# Audio-2.net
KiCad netlist of a schematic drawn in EAGLE
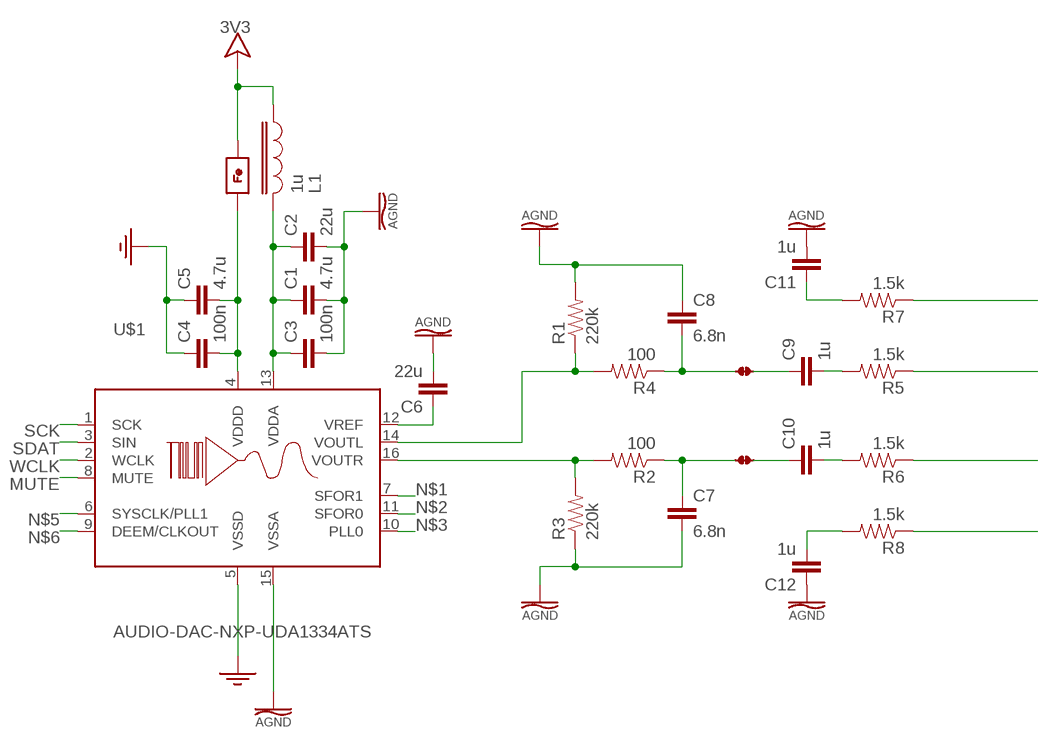
[diagram p0: schematic, sheet 1]

(export (version "E")
  (design (tool "Eeschema 10.0.6"))
  (components
    (comp (ref "C1")
      (value "4.7u")
      (footprint "eagle-import:0805-WIDE")
      (libsource (lib "eagle-import") (part "CAP-0805-WIDE"))
    )
    (comp (ref "C2")
      (value "22u")
      (footprint "eagle-import:1206-MIN")
      (libsource (lib "eagle-import") (part "CAP-1206-MIN"))
    )
    (comp (ref "C3")
      (value "100n")
      (footprint "eagle-import:0402")
      (libsource (lib "eagle-import") (part "CAP-0402"))
    )
    (comp (ref "C4")
      (value "100n")
      (footprint "eagle-import:0402")
      (libsource (lib "eagle-import") (part "CAP-0402"))
    )
    (comp (ref "C5")
      (value "4.7u")
      (footprint "eagle-import:0805-WIDE")
      (libsource (lib "eagle-import") (part "CAP-0805-WIDE"))
    )
    (comp (ref "C6")
      (value "22u")
      (footprint "eagle-import:1206-MIN")
      (libsource (lib "eagle-import") (part "CAP-1206-MIN"))
    )
    (comp (ref "C7")
      (value "6.8n")
      (footprint "eagle-import:0603")
      (libsource (lib "eagle-import") (part "CAP-0603"))
    )
    (comp (ref "C8")
      (value "6.8n")
      (footprint "eagle-import:0603")
      (libsource (lib "eagle-import") (part "CAP-0603"))
    )
    (comp (ref "C9")
      (value "1u")
      (footprint "eagle-import:0603")
      (libsource (lib "eagle-import") (part "CAP-0603"))
    )
    (comp (ref "C10")
      (value "1u")
      (footprint "eagle-import:0603")
      (libsource (lib "eagle-import") (part "CAP-0603"))
    )
    (comp (ref "C11")
      (value "1u")
      (footprint "eagle-import:0603")
      (libsource (lib "eagle-import") (part "CAP-0603"))
    )
    (comp (ref "C12")
      (value "1u")
      (footprint "eagle-import:0603")
      (libsource (lib "eagle-import") (part "CAP-0603"))
    )
    (comp (ref "FB1")
      (value "FERRITE-BEAD-0603-MIN")
      (footprint "eagle-import:0603-MIN")
      (libsource (lib "eagle-import") (part "FERRITE-BEAD-0603-MIN"))
    )
    (comp (ref "J1")
      (value "JUMPER-0805")
      (footprint "eagle-import:0805-JUMPER")
      (libsource (lib "eagle-import") (part "JUMPER-0805"))
    )
    (comp (ref "J2")
      (value "JUMPER-0805")
      (footprint "eagle-import:0805-JUMPER")
      (libsource (lib "eagle-import") (part "JUMPER-0805"))
    )
    (comp (ref "L1")
      (value "1u")
      (footprint "eagle-import:0805-MIN")
      (libsource (lib "eagle-import") (part "INDUCTOR-0805-MIN"))
    )
    (comp (ref "R1")
      (value "220k")
      (footprint "eagle-import:0603")
      (libsource (lib "eagle-import") (part "RESISTOR-0603"))
    )
    (comp (ref "R2")
      (value "100")
      (footprint "eagle-import:0603")
      (libsource (lib "eagle-import") (part "RESISTOR-0603"))
    )
    (comp (ref "R3")
      (value "220k")
      (footprint "eagle-import:0603")
      (libsource (lib "eagle-import") (part "RESISTOR-0603"))
    )
    (comp (ref "R4")
      (value "100")
      (footprint "eagle-import:0603")
      (libsource (lib "eagle-import") (part "RESISTOR-0603"))
    )
    (comp (ref "R5")
      (value "1.5k")
      (footprint "eagle-import:0603")
      (libsource (lib "eagle-import") (part "RESISTOR-0603"))
    )
    (comp (ref "R6")
      (value "1.5k")
      (footprint "eagle-import:0603")
      (libsource (lib "eagle-import") (part "RESISTOR-0603"))
    )
    (comp (ref "R7")
      (value "1.5k")
      (footprint "eagle-import:0603")
      (libsource (lib "eagle-import") (part "RESISTOR-0603"))
    )
    (comp (ref "R8")
      (value "1.5k")
      (footprint "eagle-import:0603")
      (libsource (lib "eagle-import") (part "RESISTOR-0603"))
    )
    (comp (ref "U$1")
      (value "AUDIO-DAC-NXP-UDA1334ATS")
      (footprint "eagle-import:TSSOP16")
      (libsource (lib "eagle-import") (part "AUDIO-DAC-NXP-UDA1334ATS"))
    )
  )
  (nets
    (net (code "1") (name "/MUTE") (class "Default")
      (node (ref "U$1") (pin "8") (pinfunction "MUTE_8") (pintype "bidirectional"))
    )
    (net (code "2") (name "/N$1") (class "Default")
      (node (ref "U$1") (pin "7") (pinfunction "SFOR1_7") (pintype "bidirectional"))
    )
    (net (code "3") (name "/N$2") (class "Default")
      (node (ref "U$1") (pin "11") (pinfunction "SFOR0_11") (pintype "bidirectional"))
    )
    (net (code "4") (name "/N$3") (class "Default")
      (node (ref "U$1") (pin "10") (pinfunction "PLL0_10") (pintype "bidirectional"))
    )
    (net (code "5") (name "/N$5") (class "Default")
      (node (ref "U$1") (pin "6") (pinfunction "SYSCLK/PLL1_6") (pintype "bidirectional"))
    )
    (net (code "6") (name "/N$6") (class "Default")
      (node (ref "U$1") (pin "9") (pinfunction "DEEM/CLKOUT_9") (pintype "bidirectional"))
    )
    (net (code "7") (name "/SCK") (class "Default")
      (node (ref "U$1") (pin "1") (pinfunction "SCK_1") (pintype "bidirectional"))
    )
    (net (code "8") (name "/SDAT") (class "Default")
      (node (ref "U$1") (pin "3") (pinfunction "SIN_3") (pintype "bidirectional"))
    )
    (net (code "9") (name "/WCLK") (class "Default")
      (node (ref "U$1") (pin "2") (pinfunction "WCLK_2") (pintype "bidirectional"))
    )
    (net (code "10") (name "AGND") (class "Default")
      (node (ref "C1") (pin "1") (pinfunction "1_1") (pintype "bidirectional"))
      (node (ref "C11") (pin "1") (pinfunction "1_1") (pintype "bidirectional"))
      (node (ref "C12") (pin "2") (pinfunction "2_2") (pintype "bidirectional"))
      (node (ref "C2") (pin "1") (pinfunction "1_1") (pintype "bidirectional"))
      (node (ref "C3") (pin "1") (pinfunction "1_1") (pintype "bidirectional"))
      (node (ref "C6") (pin "1") (pinfunction "1_1") (pintype "bidirectional"))
      (node (ref "C7") (pin "1") (pinfunction "1_1") (pintype "bidirectional"))
      (node (ref "C8") (pin "2") (pinfunction "2_2") (pintype "bidirectional"))
      (node (ref "R1") (pin "2") (pinfunction "2_2") (pintype "passive"))
      (node (ref "R3") (pin "1") (pinfunction "1_1") (pintype "passive"))
      (node (ref "U$1") (pin "15") (pinfunction "VSSA_15") (pintype "bidirectional"))
    )
    (net (code "11") (name "GND") (class "Default")
      (node (ref "C4") (pin "2") (pinfunction "2_2") (pintype "bidirectional"))
      (node (ref "C5") (pin "2") (pinfunction "2_2") (pintype "bidirectional"))
      (node (ref "U$1") (pin "5") (pinfunction "VSSD_5") (pintype "bidirectional"))
    )
    (net (code "12") (name "Net-(C7-Pad2)") (class "Default")
      (node (ref "C7") (pin "2") (pinfunction "2_2") (pintype "bidirectional"))
      (node (ref "J2") (pin "1") (pinfunction "1_1") (pintype "bidirectional"))
      (node (ref "R2") (pin "1") (pinfunction "1_1") (pintype "passive"))
    )
    (net (code "13") (name "Net-(C8-Pad1)") (class "Default")
      (node (ref "C8") (pin "1") (pinfunction "1_1") (pintype "bidirectional"))
      (node (ref "J1") (pin "1") (pinfunction "1_1") (pintype "bidirectional"))
      (node (ref "R4") (pin "1") (pinfunction "1_1") (pintype "passive"))
    )
    (net (code "14") (name "Net-(C9-Pad1)") (class "Default")
      (node (ref "C9") (pin "1") (pinfunction "1_1") (pintype "bidirectional"))
      (node (ref "R5") (pin "2") (pinfunction "2_2") (pintype "passive"))
    )
    (net (code "15") (name "Net-(C9-Pad2)") (class "Default")
      (node (ref "C9") (pin "2") (pinfunction "2_2") (pintype "bidirectional"))
      (node (ref "J1") (pin "2") (pinfunction "2_2") (pintype "bidirectional"))
    )
    (net (code "16") (name "Net-(C10-Pad1)") (class "Default")
      (node (ref "C10") (pin "1") (pinfunction "1_1") (pintype "bidirectional"))
      (node (ref "R6") (pin "2") (pinfunction "2_2") (pintype "passive"))
    )
    (net (code "17") (name "Net-(C10-Pad2)") (class "Default")
      (node (ref "C10") (pin "2") (pinfunction "2_2") (pintype "bidirectional"))
      (node (ref "J2") (pin "2") (pinfunction "2_2") (pintype "bidirectional"))
    )
    (net (code "18") (name "Net-(C11-Pad2)") (class "Default")
      (node (ref "C11") (pin "2") (pinfunction "2_2") (pintype "bidirectional"))
      (node (ref "R7") (pin "2") (pinfunction "2_2") (pintype "passive"))
    )
    (net (code "19") (name "Net-(C12-Pad1)") (class "Default")
      (node (ref "C12") (pin "1") (pinfunction "1_1") (pintype "bidirectional"))
      (node (ref "R8") (pin "2") (pinfunction "2_2") (pintype "passive"))
    )
    (net (code "20") (name "Net-(U$1-VDDA)") (class "Default")
      (node (ref "C1") (pin "2") (pinfunction "2_2") (pintype "bidirectional"))
      (node (ref "C2") (pin "2") (pinfunction "2_2") (pintype "bidirectional"))
      (node (ref "C3") (pin "2") (pinfunction "2_2") (pintype "bidirectional"))
      (node (ref "L1") (pin "1") (pinfunction "1_1") (pintype "bidirectional"))
      (node (ref "U$1") (pin "13") (pinfunction "VDDA_13") (pintype "bidirectional"))
    )
    (net (code "21") (name "Net-(U$1-VDDD)") (class "Default")
      (node (ref "C4") (pin "1") (pinfunction "1_1") (pintype "bidirectional"))
      (node (ref "C5") (pin "1") (pinfunction "1_1") (pintype "bidirectional"))
      (node (ref "FB1") (pin "1") (pinfunction "1_1") (pintype "bidirectional"))
      (node (ref "U$1") (pin "4") (pinfunction "VDDD_4") (pintype "bidirectional"))
    )
    (net (code "22") (name "Net-(U$1-VOUTL)") (class "Default")
      (node (ref "R1") (pin "1") (pinfunction "1_1") (pintype "passive"))
      (node (ref "R4") (pin "2") (pinfunction "2_2") (pintype "passive"))
      (node (ref "U$1") (pin "14") (pinfunction "VOUTL_14") (pintype "bidirectional"))
    )
    (net (code "23") (name "Net-(U$1-VOUTR)") (class "Default")
      (node (ref "R2") (pin "2") (pinfunction "2_2") (pintype "passive"))
      (node (ref "R3") (pin "2") (pinfunction "2_2") (pintype "passive"))
      (node (ref "U$1") (pin "16") (pinfunction "VOUTR_16") (pintype "bidirectional"))
    )
    (net (code "24") (name "Net-(U$1-VREF)") (class "Default")
      (node (ref "C6") (pin "2") (pinfunction "2_2") (pintype "bidirectional"))
      (node (ref "U$1") (pin "12") (pinfunction "VREF_12") (pintype "bidirectional"))
    )
    (net (code "25") (name "V") (class "Default")
      (node (ref "FB1") (pin "2") (pinfunction "2_2") (pintype "bidirectional"))
      (node (ref "L1") (pin "2") (pinfunction "2_2") (pintype "bidirectional"))
    )
    (net (code "26") (name "unconnected-(R5-Pad1)") (class "Default")
      (node (ref "R5") (pin "1") (pinfunction "1_1") (pintype "passive"))
    )
    (net (code "27") (name "unconnected-(R6-Pad1)") (class "Default")
      (node (ref "R6") (pin "1") (pinfunction "1_1") (pintype "passive"))
    )
    (net (code "28") (name "unconnected-(R7-Pad1)") (class "Default")
      (node (ref "R7") (pin "1") (pinfunction "1_1") (pintype "passive"))
    )
    (net (code "29") (name "unconnected-(R8-Pad1)") (class "Default")
      (node (ref "R8") (pin "1") (pinfunction "1_1") (pintype "passive"))
    )
  )
)
